# Efield1A.net
KiCad netlist of a schematic drawn in EAGLE
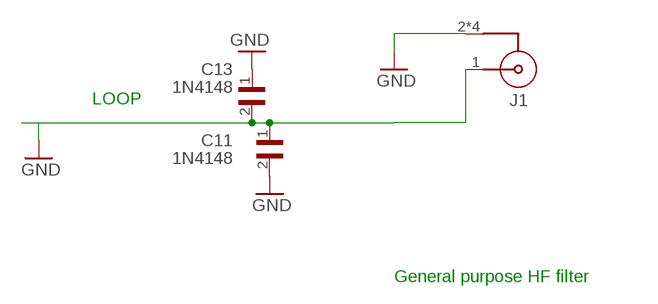
[diagram p0: schematic, sheet 1]

(export (version "E")
  (design (tool "Eeschema 10.0.6"))
  (components
    (comp (ref "C11")
      (value "1N4148")
      (footprint "eagle-import:WCAP-CSGP_0805_REFLOW")
      (libsource (lib "eagle-import") (part "WCAP-CSGP_0805-REFLOW"))
    )
    (comp (ref "C13")
      (value "1N4148")
      (footprint "eagle-import:WCAP-CSGP_0805_REFLOW")
      (libsource (lib "eagle-import") (part "WCAP-CSGP_0805-REFLOW"))
    )
    (comp (ref "J1")
      (value "60312202114509")
      (footprint "eagle-import:60312202114509")
      (libsource (lib "eagle-import") (part "60312202114509"))
    )
  )
  (nets
    (net (code "1") (name "GND") (class "Default")
      (node (ref "C11") (pin "1") (pinfunction "1_1") (pintype "passive"))
      (node (ref "C11") (pin "2") (pinfunction "2_2") (pintype "passive"))
      (node (ref "C13") (pin "1") (pinfunction "1_1") (pintype "passive"))
      (node (ref "C13") (pin "2") (pinfunction "2_2") (pintype "passive"))
      (node (ref "J1") (pin "1") (pinfunction "1_1") (pintype "passive"))
      (node (ref "J1") (pin "2") (pinfunction "2_2") (pintype "passive"))
      (node (ref "J1") (pin "3") (pinfunction "2_3") (pintype "passive"))
      (node (ref "J1") (pin "4") (pinfunction "2_4") (pintype "passive"))
      (node (ref "J1") (pin "5") (pinfunction "2_5") (pintype "passive"))
    )
  )
)
